# MC21R01_Power.net
KiCad netlist of a schematic drawn in Altium Designer
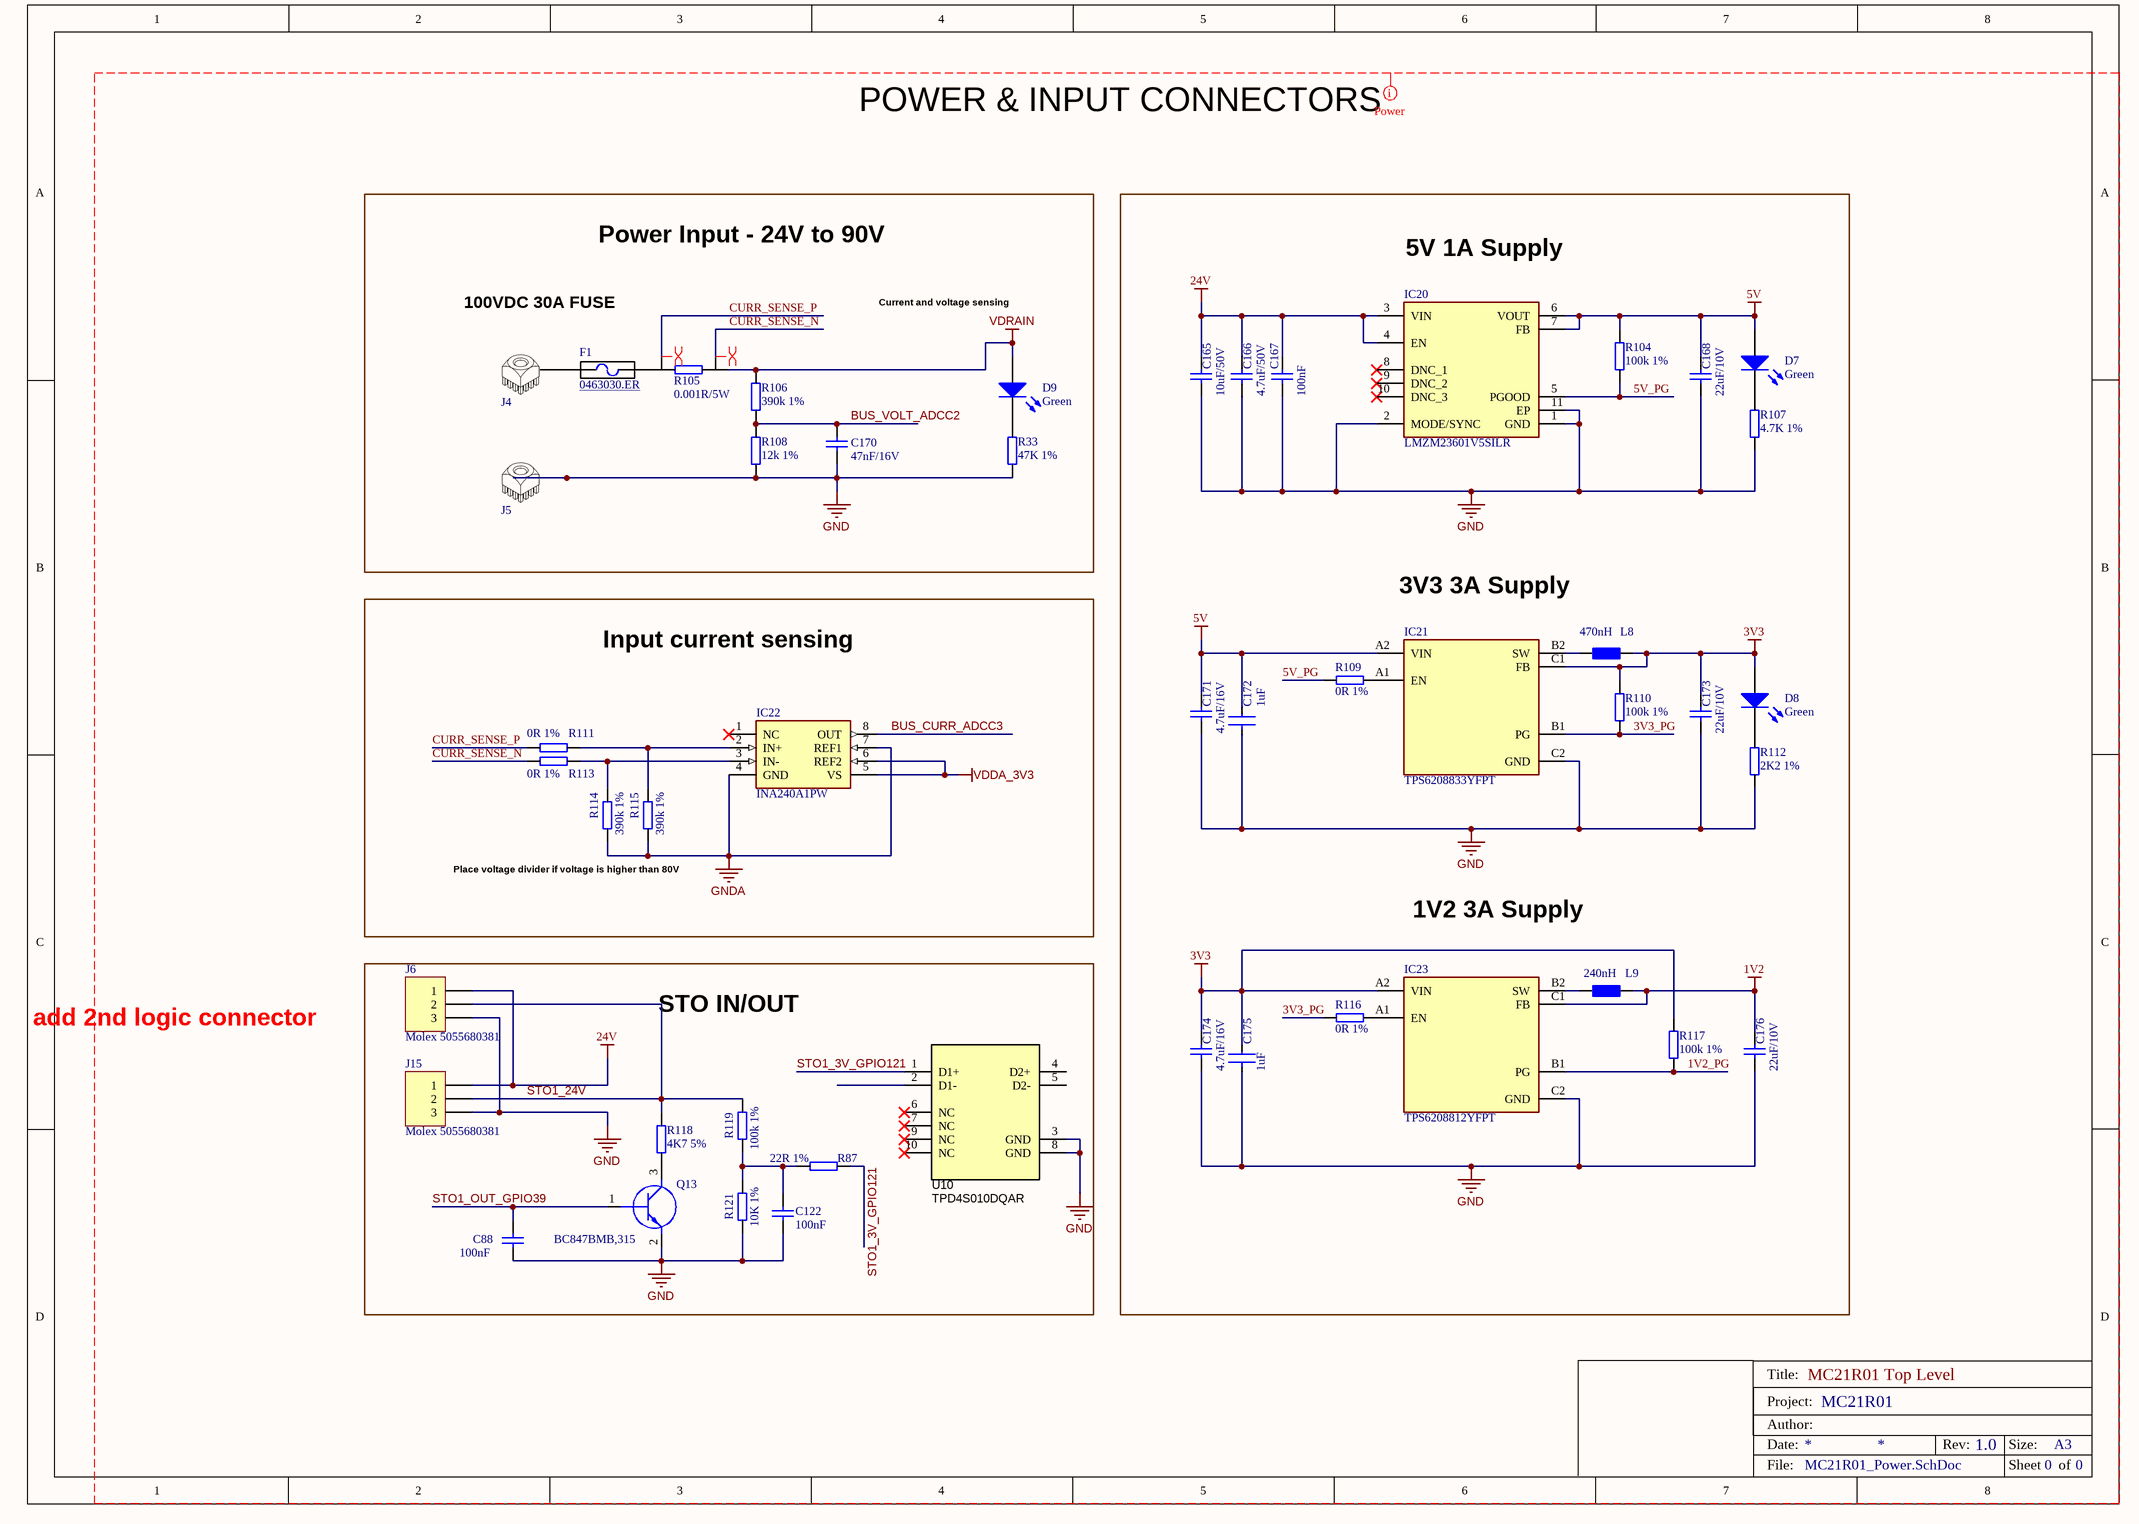
[diagram p0: MC21R01_Power.SchDoc]

(export (version "E")
  (design (tool "Eeschema 10.0.6"))
  (components
    (comp (ref "C88")
      (value "100nF")
      (footprint "CAPC0603X03N")
      (description "100nF/25V 0201 10% Tolerance X6S Multilayer Ceramic Chip Capacitor")
      (fields (field (name "TOLERANCE") "10%") (field (name "Comment") "100nF/25V 0201 10% X6S"))
      (libsource (lib "Wandercraft") (part "STD_CAP_2PIN_NPOL"))
    )
    (comp (ref "C122")
      (value "100nF")
      (footprint "CAPC0603X03N")
      (description "100nF/25V 0201 10% Tolerance X6S Multilayer Ceramic Chip Capacitor")
      (fields (field (name "TOLERANCE") "10%") (field (name "Comment") "100nF/25V 0201 10% X6S"))
      (libsource (lib "Wandercraft") (part "STD_CAP_2PIN_NPOL"))
    )
    (comp (ref "C165")
      (value "10uF/50V")
      (footprint "PAL_Capacitors:1206 SMD Capacitor")
      (description "10 uF 50 V 1206 ±10% Tolerance X5R Multilayer Ceramic Chip Capacitor")
      (fields (field (name "Comment") "10uf/50V 1206 10% X5R"))
      (libsource (lib "PAL_Capacitors") (part "10uF/50V 1206 10% X5R"))
    )
    (comp (ref "C166")
      (value "4.7uF/50V")
      (footprint "PAL_Capacitors:0805 SMD capacitor")
      (description "4.7uF 50 V 0805 ±10% Tolerance X5R Multilayer Ceramic Chip Capacitor")
      (fields (field (name "Comment") "4.7uf/50V 0805 10% X5R"))
      (libsource (lib "PAL_Capacitors") (part "4.7uF/50V 0805 10% X5R"))
    )
    (comp (ref "C167")
      (value "100nF")
      (footprint "CAPC0603X03N")
      (description "100nF/25V 0201 10% Tolerance X6S Multilayer Ceramic Chip Capacitor")
      (fields (field (name "TOLERANCE") "10%") (field (name "Comment") "100nF/25V 0201 10% X6S"))
      (libsource (lib "Wandercraft") (part "STD_CAP_2PIN_NPOL"))
    )
    (comp (ref "C168")
      (value "22uF/10V")
      (footprint "PAL_Capacitors:0603 SMD capacitor")
      (description "22 uF 10 V 0603 ±20% Tolerance X5R Multilayer Ceramic Chip Capacitor")
      (fields (field (name "Comment") "22uF/10V 0603 20% X5R"))
      (libsource (lib "PAL_Capacitors") (part "22uF/10V 0603 20% X5R"))
    )
    (comp (ref "C170")
      (value "47nF/16V")
      (footprint "PAL_Capacitors:0402 SMD Capacitor")
      (description "47nF/16V 0402 10% Tolerance X7R Multilayer Ceramic Chip Capacitor")
      (fields (field (name "Comment") "47nF/16V 0402 10% X7R"))
      (libsource (lib "PAL_Capacitors") (part "47nF/16V 0402 10% X7R"))
    )
    (comp (ref "C171")
      (value "4.7uF/16V")
      (footprint "PAL_Capacitors:0603 SMD capacitor")
      (description "4.7uF/16V 0603 10% Tolerance X5R Multilayer Ceramic Chip Capacitor")
      (fields (field (name "Comment") "4.7uF/16V 0603 10% X5R"))
      (libsource (lib "PAL_Capacitors") (part "4.7uF/16V 0603 10% X5R"))
    )
    (comp (ref "C172")
      (value "1uF/6.3V 0201 10% X5R")
      (footprint "FP-CL03-IPC_A")
      (description "1uF/6.3V 0201 10% Tolerance X5R Multilayer Ceramic Chip Capacitor")
      (fields (field (name "TOLERANCE") "20%") (field (name "CAPACITANCE") "1uF"))
      (libsource (lib "Altium Content Vault") (part "b4654b650e69147ec39a6b967a45e02"))
    )
    (comp (ref "C173")
      (value "22uF/10V")
      (footprint "PAL_Capacitors:0603 SMD capacitor")
      (description "22 uF 10 V 0603 ±20% Tolerance X5R Multilayer Ceramic Chip Capacitor")
      (fields (field (name "Comment") "22uF/10V 0603 20% X5R"))
      (libsource (lib "PAL_Capacitors") (part "22uF/10V 0603 20% X5R"))
    )
    (comp (ref "C174")
      (value "4.7uF/16V")
      (footprint "PAL_Capacitors:0603 SMD capacitor")
      (description "4.7uF/16V 0603 10% Tolerance X5R Multilayer Ceramic Chip Capacitor")
      (fields (field (name "Comment") "4.7uF/16V 0603 10% X5R"))
      (libsource (lib "PAL_Capacitors") (part "4.7uF/16V 0603 10% X5R"))
    )
    (comp (ref "C175")
      (value "1uF/6.3V 0201 10% X5R")
      (footprint "FP-CL03-IPC_A")
      (description "1uF/6.3V 0201 10% Tolerance X5R Multilayer Ceramic Chip Capacitor")
      (fields (field (name "TOLERANCE") "20%") (field (name "CAPACITANCE") "1uF"))
      (libsource (lib "Altium Content Vault") (part "b4654b650e69147ec39a6b967a45e02"))
    )
    (comp (ref "C176")
      (value "22uF/10V")
      (footprint "PAL_Capacitors:0603 SMD capacitor")
      (description "22 uF 10 V 0603 ±20% Tolerance X5R Multilayer Ceramic Chip Capacitor")
      (fields (field (name "Comment") "22uF/10V 0603 20% X5R"))
      (libsource (lib "PAL_Capacitors") (part "22uF/10V 0603 20% X5R"))
    )
    (comp (ref "D7")
      (value "Green")
      (footprint "0402 SMD LED GREEN")
      (description "Low Profile Chip LED, Green")
      (fields (field (name "MANUFACTURER") "ROHM") (field (name "MANUFACTURER PART NUMBER") "SML-P11MTT86R"))
      (libsource (lib "PAL_devices") (part "LED_0402_green"))
    )
    (comp (ref "D8")
      (value "Green")
      (footprint "0402 SMD LED GREEN")
      (description "Low Profile Chip LED, Green")
      (fields (field (name "MANUFACTURER") "ROHM") (field (name "MANUFACTURER PART NUMBER") "SML-P11MTT86R"))
      (libsource (lib "PAL_devices") (part "LED_0402_green"))
    )
    (comp (ref "D9")
      (value "Green")
      (footprint "0402 SMD LED GREEN")
      (description "Low Profile Chip LED, Green")
      (fields (field (name "MANUFACTURER") "ROHM") (field (name "MANUFACTURER PART NUMBER") "SML-P11MTT86R"))
      (libsource (lib "PAL_devices") (part "LED_0402_green"))
    )
    (comp (ref "F1")
      (value "0463030.ER")
      (footprint "0463030.ER")
      (description "LITTELFUSE - 0463030.ER - 100VDC 30A FUSE SMD")
      (libsource (lib "PAL_devices") (part "0463030.ER"))
    )
    (comp (ref "IC20")
      (value "LMZM23601V5SILR")
      (footprint "PAL_devices:LMZM23601V5SILR")
      (description "5V 1A Step-down regulator. 4V to 36V input, 5V fixed output")
      (libsource (lib "PAL_devices") (part "LMZM23601V5SILR"))
    )
    (comp (ref "IC21")
      (value "TPS6208833YFPT")
      (footprint "PAL_IPC-7351B_Footprints:BGA6C40P2X3_80X120X50")
      (description "3.3V 3A Step-Down converter")
      (libsource (lib "PAL_devices") (part "TPS6208833YFPT"))
    )
    (comp (ref "IC22")
      (value "INA240A1PW")
      (footprint "PAL_IPC-7351B_Footprints:SOP65P640X120-8N")
      (description "20V/V current sense amplifier")
      (libsource (lib "PAL_devices") (part "INA240A1PW"))
    )
    (comp (ref "IC23")
      (value "TPS6208812YFPT")
      (footprint "PAL_IPC-7351B_Footprints:BGA6C40P2X3_80X120X50")
      (description "1.2V 3A Step-Down converter")
      (libsource (lib "PAL_devices") (part "TPS6208812YFPT"))
    )
    (comp (ref "J4")
      (value "WE_7461094")
      (footprint "WE_7461094")
      (description "REDCUBE PRESS-FIT with external thread and full plain pin-plate WPSHFU, 130A, M3 screw, 9pins")
      (fields
        (field (name "MANUFACTURER") "WURTH ELEKTRONIK")
        (field (name "MANUFACTURER PART NUMBER") "7461094")
        (field (name "CREATED BY") "Yaiza Montes")
      )
      (libsource (lib "PAL_Wurth_2020") (part "WE_7461094"))
    )
    (comp (ref "J5")
      (value "WE_7461094")
      (footprint "WE_7461094")
      (description "REDCUBE PRESS-FIT with external thread and full plain pin-plate WPSHFU, 130A, M3 screw, 9pins")
      (fields
        (field (name "MANUFACTURER") "WURTH ELEKTRONIK")
        (field (name "MANUFACTURER PART NUMBER") "7461094")
        (field (name "CREATED BY") "Yaiza Montes")
      )
      (libsource (lib "PAL_Wurth_2020") (part "WE_7461094"))
    )
    (comp (ref "J6")
      (value "Molex 5055680381")
      (footprint "Molex 5055680381")
      (fields
        (field (name "MANUFACTURER") "Molex")
        (field (name "MANUFACTURER PART NUMBER") "5055680381")
        (field (name "MATING PART NUMBER") "Molex 5055650301")
        (field (name "CREATED BY") "Yaiza Montes")
      )
      (libsource (lib "PAL_Molex_Micro-Lock_2020") (part "Molex 5055680381"))
    )
    (comp (ref "J15")
      (value "Molex 5055680381")
      (footprint "Molex 5055680381")
      (fields
        (field (name "MANUFACTURER") "Molex")
        (field (name "MANUFACTURER PART NUMBER") "5055680381")
        (field (name "MATING PART NUMBER") "Molex 5055650301")
        (field (name "CREATED BY") "Yaiza Montes")
      )
      (libsource (lib "PAL_Molex_Micro-Lock_2020") (part "Molex 5055680381"))
    )
    (comp (ref "L8")
      (value "470nH")
      (footprint "PAL_Inductors:0603 SMD inductor")
      (description "Inductor, 470nH, 0603 [1608 Metric], 2.6 A, 0.054 ohm, ± 20%")
      (fields (field (name "MPN") "DFE18SANR47MG0L") (field (name "MF") "MURATA"))
      (libsource (lib "PAL_Inductors") (part "470nH/3.2A, 0603 , 2.6 A, 0.054 ohm, ± 20%"))
    )
    (comp (ref "L9")
      (value "240nH")
      (footprint "PAL_Inductors:0603 SMD inductor")
      (description "Inductor, 240nH, 0603 [1608 Metric], 3.2 A, 0.036 ohm, ± 20%")
      (fields (field (name "MPN") "DFE18SANR24ME0L") (field (name "MF") "MURATA"))
      (libsource (lib "PAL_Inductors") (part "240nH/3.2A, 0603 , 3 A, 0.036 ohm, ± 20%"))
    )
    (comp (ref "Q13")
      (value "BC847BMB,315")
      (footprint "PAL_IPC-7351B_Footprints:SOT883B")
      (description "Transistor BJT NPN")
      (fields (field (name "MOUSER PART NUMBER") "771-BC847BMB315"))
      (libsource (lib "PAL_devices") (part "BC847BMB,315"))
    )
    (comp (ref "R33")
      (value "47K 1%")
      (footprint "0402 SMD rESISTOR")
      (description "47K/50V 1% 0402 100mW SMD Resistor")
      (libsource (lib "PAL_Resistors") (part "47K/50V 1% 0402 100mW"))
    )
    (comp (ref "R87")
      (value "22R 1%")
      (footprint "0402 SMD rESISTOR")
      (description "22R/50V 1% 0402 63mW SMD Resistor")
      (libsource (lib "PAL_Resistors") (part "22R/50V 1% 0402 63mW"))
    )
    (comp (ref "R104")
      (value "100k 1%")
      (footprint "0402 SMD rESISTOR")
      (description "100k/50V 1% 0402 100mW SMD Resistor")
      (libsource (lib "PAL_Resistors") (part "100k/50V 1% 0402 100mW"))
    )
    (comp (ref "R105")
      (value "0.001R/5W")
      (footprint "PAL_Resistors:2512 SMD Resistor V2 NETTIE")
      (description "0.001R/5W 1% 2512 shunt SMD Resistor")
      (libsource (lib "PAL_Resistors") (part "0.001R/5W 1% 2512 Shunt"))
    )
    (comp (ref "R106")
      (value "390k 1%")
      (footprint "PAL_Resistors:0603 SMD resistor")
      (description "390k/150V 1% 0603 250mW SMD Resistor")
      (libsource (lib "PAL_Resistors") (part "390k/150V 1% 0603 250mW"))
    )
    (comp (ref "R107")
      (value "4.7K 1%")
      (footprint "0402 SMD rESISTOR")
      (description "4.7K/50V 1% 0402 100mW SMD Resistor")
      (libsource (lib "PAL_Resistors") (part "4.7K/50V 1% 0402 100mW"))
    )
    (comp (ref "R108")
      (value "12k 1%")
      (footprint "PAL_Resistors:0603 SMD resistor")
      (description "12k/150V 1% 0603 250mW SMD Resistor")
      (libsource (lib "PAL_Resistors") (part "12k/150V 1% 0603 250mW"))
    )
    (comp (ref "R109")
      (value "0R 1%")
      (footprint "0402 SMD rESISTOR")
      (description "0R/50V 1% 0402 100mW SMD Resistor")
      (libsource (lib "PAL_Resistors") (part "0R/50V 1% 0402 100mW"))
    )
    (comp (ref "R110")
      (value "100k 1%")
      (footprint "0402 SMD rESISTOR")
      (description "100k/50V 1% 0402 100mW SMD Resistor")
      (libsource (lib "PAL_Resistors") (part "100k/50V 1% 0402 100mW"))
    )
    (comp (ref "R111")
      (value "0R 1%")
      (footprint "0402 SMD rESISTOR")
      (description "0R/100V 1% 0402 63mW SMD Resistor")
      (libsource (lib "PAL_Resistors") (part "0R/100V 1% 0402 63mW"))
    )
    (comp (ref "R112")
      (value "2K2 1%")
      (footprint "0402 SMD rESISTOR")
      (description "2K2/50V 1% 0402 100mW SMD Resistor")
      (libsource (lib "PAL_Resistors") (part "2K2/50V 1% 0402 100mW"))
    )
    (comp (ref "R113")
      (value "0R 1%")
      (footprint "0402 SMD rESISTOR")
      (description "0R/100V 1% 0402 63mW SMD Resistor")
      (libsource (lib "PAL_Resistors") (part "0R/100V 1% 0402 63mW"))
    )
    (comp (ref "R114")
      (value "390k 1%")
      (footprint "PAL_Resistors:0603 SMD resistor")
      (description "390k/150V 1% 0603 250mW SMD Resistor")
      (libsource (lib "PAL_Resistors") (part "390k/150V 1% 0603 250mW"))
    )
    (comp (ref "R115")
      (value "390k 1%")
      (footprint "PAL_Resistors:0603 SMD resistor")
      (description "390k/150V 1% 0603 250mW SMD Resistor")
      (libsource (lib "PAL_Resistors") (part "390k/150V 1% 0603 250mW"))
    )
    (comp (ref "R116")
      (value "0R 1%")
      (footprint "0402 SMD rESISTOR")
      (description "0R/50V 1% 0402 100mW SMD Resistor")
      (libsource (lib "PAL_Resistors") (part "0R/50V 1% 0402 100mW"))
    )
    (comp (ref "R117")
      (value "100k 1%")
      (footprint "0402 SMD rESISTOR")
      (description "100k/50V 1% 0402 100mW SMD Resistor")
      (libsource (lib "PAL_Resistors") (part "100k/50V 1% 0402 100mW"))
    )
    (comp (ref "R118")
      (value "4K7 5%")
      (footprint "PAL_Resistors:0603 SMD resistor")
      (description "4K7/75V 5% 0603 100mW SMD Resistor")
      (libsource (lib "PAL_Resistors") (part "4K7/75V 5% 0603 100mW"))
    )
    (comp (ref "R119")
      (value "100k 1%")
      (footprint "0402 SMD rESISTOR")
      (description "100k/50V 1% 0402 100mW SMD Resistor")
      (libsource (lib "PAL_Resistors") (part "100k/50V 1% 0402 100mW"))
    )
    (comp (ref "R121")
      (value "10K 1%")
      (footprint "0402 SMD rESISTOR")
      (description "10K/50V 1% 0402 100mW SMD Resistor")
      (libsource (lib "PAL_Resistors") (part "10K/50V 1% 0402 100mW"))
    )
    (comp (ref "U10")
      (value "TPD4S010DQAR")
      (footprint "DQA0010A")
      (fields (field (name "MANUFACTURER") "Texas Instruments") (field (name "PARTNUMBER") "TPD4S010DQAR"))
      (libsource (lib "PAL_devices") (part "TPD4S010DQAR"))
    )
  )
  (nets
    (net (code "1") (name "/1V2_PG") (class "Default")
      (node (ref "IC23") (pin "B1") (pinfunction "PG_B1") (pintype "passive"))
      (node (ref "R117") (pin "1") (pinfunction "1_1") (pintype "passive"))
    )
    (net (code "2") (name "/3V3_PG") (class "Default")
      (node (ref "IC21") (pin "B1") (pinfunction "PG_B1") (pintype "passive"))
      (node (ref "R110") (pin "1") (pinfunction "1_1") (pintype "passive"))
      (node (ref "R116") (pin "2") (pinfunction "2_2") (pintype "passive"))
    )
    (net (code "3") (name "/5V_PG") (class "Default")
      (node (ref "IC20") (pin "5") (pinfunction "PGOOD_5") (pintype "passive"))
      (node (ref "R104") (pin "1") (pinfunction "1_1") (pintype "passive"))
      (node (ref "R109") (pin "2") (pinfunction "2_2") (pintype "passive"))
    )
    (net (code "4") (name "/BUS_CURR_ADCC3") (class "Default")
      (node (ref "IC22") (pin "8") (pinfunction "OUT_8") (pintype "output"))
    )
    (net (code "5") (name "/BUS_VOLT_ADCC2") (class "Default")
      (node (ref "C170") (pin "1") (pinfunction "1_1") (pintype "passive"))
      (node (ref "R106") (pin "1") (pinfunction "1_1") (pintype "passive"))
      (node (ref "R108") (pin "2") (pinfunction "2_2") (pintype "passive"))
    )
    (net (code "6") (name "/CURR_SENSE_N") (class "Default")
      (node (ref "R105") (pin "3") (pinfunction "3_3") (pintype "passive"))
      (node (ref "R113") (pin "1") (pinfunction "1_1") (pintype "passive"))
    )
    (net (code "7") (name "/CURR_SENSE_P") (class "Default")
      (node (ref "R105") (pin "4") (pinfunction "4_4") (pintype "passive"))
      (node (ref "R111") (pin "2") (pinfunction "2_2") (pintype "passive"))
    )
    (net (code "8") (name "/STO1_3V_GPIO121") (class "Default")
      (node (ref "R87") (pin "1") (pinfunction "1_1") (pintype "passive"))
      (node (ref "U10") (pin "1") (pinfunction "D1+_1") (pintype "passive"))
    )
    (net (code "9") (name "/STO1_24V") (class "Default")
      (node (ref "J15") (pin "2") (pinfunction "2_2") (pintype "passive"))
      (node (ref "J6") (pin "2") (pinfunction "2_2") (pintype "passive"))
      (node (ref "R118") (pin "2") (pinfunction "2_2") (pintype "passive"))
      (node (ref "R119") (pin "2") (pinfunction "2_2") (pintype "passive"))
    )
    (net (code "10") (name "/STO1_OUT_GPIO39") (class "Default")
      (node (ref "C88") (pin "2") (pinfunction "2_2") (pintype "passive"))
      (node (ref "Q13") (pin "1") (pinfunction "B_1") (pintype "passive"))
    )
    (net (code "11") (name "1V2") (class "Default")
      (node (ref "C176") (pin "1") (pinfunction "1_1") (pintype "passive"))
      (node (ref "IC23") (pin "C1") (pinfunction "FB_C1") (pintype "passive"))
      (node (ref "L9") (pin "1") (pinfunction "1_1") (pintype "passive"))
    )
    (net (code "12") (name "3V3") (class "Default")
      (node (ref "C173") (pin "1") (pinfunction "1_1") (pintype "passive"))
      (node (ref "C174") (pin "1") (pinfunction "1_1") (pintype "passive"))
      (node (ref "C175") (pin "2") (pinfunction "2_2") (pintype "passive"))
      (node (ref "D8") (pin "A") (pinfunction "A_A") (pintype "passive"))
      (node (ref "IC21") (pin "C1") (pinfunction "FB_C1") (pintype "passive"))
      (node (ref "IC23") (pin "A2") (pinfunction "VIN_A2") (pintype "passive"))
      (node (ref "L8") (pin "1") (pinfunction "1_1") (pintype "passive"))
      (node (ref "R110") (pin "2") (pinfunction "2_2") (pintype "passive"))
      (node (ref "R117") (pin "2") (pinfunction "2_2") (pintype "passive"))
    )
    (net (code "13") (name "5V") (class "Default")
      (node (ref "C168") (pin "1") (pinfunction "1_1") (pintype "passive"))
      (node (ref "C171") (pin "1") (pinfunction "1_1") (pintype "passive"))
      (node (ref "C172") (pin "2") (pinfunction "2_2") (pintype "passive"))
      (node (ref "D7") (pin "A") (pinfunction "A_A") (pintype "passive"))
      (node (ref "IC20") (pin "6") (pinfunction "VOUT_6") (pintype "passive"))
      (node (ref "IC20") (pin "7") (pinfunction "FB_7") (pintype "passive"))
      (node (ref "IC21") (pin "A2") (pinfunction "VIN_A2") (pintype "passive"))
      (node (ref "R104") (pin "2") (pinfunction "2_2") (pintype "passive"))
    )
    (net (code "14") (name "24V") (class "Default")
      (node (ref "C165") (pin "1") (pinfunction "1_1") (pintype "passive"))
      (node (ref "C166") (pin "1") (pinfunction "1_1") (pintype "passive"))
      (node (ref "C167") (pin "2") (pinfunction "2_2") (pintype "passive"))
      (node (ref "IC20") (pin "3") (pinfunction "VIN_3") (pintype "passive"))
      (node (ref "IC20") (pin "4") (pinfunction "EN_4") (pintype "passive"))
      (node (ref "J15") (pin "1") (pinfunction "1_1") (pintype "passive"))
      (node (ref "J6") (pin "1") (pinfunction "1_1") (pintype "passive"))
    )
    (net (code "15") (name "GND") (class "Default")
      (node (ref "C122") (pin "1") (pinfunction "1_1") (pintype "passive"))
      (node (ref "C165") (pin "2") (pinfunction "2_2") (pintype "passive"))
      (node (ref "C166") (pin "2") (pinfunction "2_2") (pintype "passive"))
      (node (ref "C167") (pin "1") (pinfunction "1_1") (pintype "passive"))
      (node (ref "C168") (pin "2") (pinfunction "2_2") (pintype "passive"))
      (node (ref "C170") (pin "2") (pinfunction "2_2") (pintype "passive"))
      (node (ref "C171") (pin "2") (pinfunction "2_2") (pintype "passive"))
      (node (ref "C172") (pin "1") (pinfunction "1_1") (pintype "passive"))
      (node (ref "C173") (pin "2") (pinfunction "2_2") (pintype "passive"))
      (node (ref "C174") (pin "2") (pinfunction "2_2") (pintype "passive"))
      (node (ref "C175") (pin "1") (pinfunction "1_1") (pintype "passive"))
      (node (ref "C176") (pin "2") (pinfunction "2_2") (pintype "passive"))
      (node (ref "C88") (pin "1") (pinfunction "1_1") (pintype "passive"))
      (node (ref "IC20") (pin "1") (pinfunction "GND_1") (pintype "passive"))
      (node (ref "IC20") (pin "11") (pinfunction "EP_11") (pintype "passive"))
      (node (ref "IC20") (pin "2") (pinfunction "MODE/SYNC_2") (pintype "passive"))
      (node (ref "IC21") (pin "C2") (pinfunction "GND_C2") (pintype "passive"))
      (node (ref "IC23") (pin "C2") (pinfunction "GND_C2") (pintype "passive"))
      (node (ref "J15") (pin "3") (pinfunction "3_3") (pintype "passive"))
      (node (ref "J5") (pin "1") (pinfunction "1_1") (pintype "passive"))
      (node (ref "J6") (pin "3") (pinfunction "3_3") (pintype "passive"))
      (node (ref "Q13") (pin "2") (pinfunction "E_2") (pintype "passive"))
      (node (ref "R107") (pin "1") (pinfunction "1_1") (pintype "passive"))
      (node (ref "R108") (pin "1") (pinfunction "1_1") (pintype "passive"))
      (node (ref "R112") (pin "1") (pinfunction "1_1") (pintype "passive"))
      (node (ref "R121") (pin "1") (pinfunction "1_1") (pintype "passive"))
      (node (ref "R33") (pin "1") (pinfunction "1_1") (pintype "passive"))
      (node (ref "U10") (pin "3") (pinfunction "GND_3") (pintype "power_in"))
      (node (ref "U10") (pin "8") (pinfunction "GND_8") (pintype "power_in"))
    )
    (net (code "16") (name "GNDA") (class "Default")
      (node (ref "IC22") (pin "4") (pinfunction "GND_4") (pintype "power_in"))
      (node (ref "IC22") (pin "7") (pinfunction "REF1_7") (pintype "input"))
      (node (ref "R114") (pin "1") (pinfunction "1_1") (pintype "passive"))
      (node (ref "R115") (pin "1") (pinfunction "1_1") (pintype "passive"))
    )
    (net (code "17") (name "Net-(C122-Pad2)") (class "Default")
      (node (ref "C122") (pin "2") (pinfunction "2_2") (pintype "passive"))
      (node (ref "R119") (pin "1") (pinfunction "1_1") (pintype "passive"))
      (node (ref "R121") (pin "2") (pinfunction "2_2") (pintype "passive"))
      (node (ref "R87") (pin "2") (pinfunction "2_2") (pintype "passive"))
    )
    (net (code "18") (name "Net-(D7-PadK)") (class "Default")
      (node (ref "D7") (pin "K") (pinfunction "K_K") (pintype "passive"))
      (node (ref "R107") (pin "2") (pinfunction "2_2") (pintype "passive"))
    )
    (net (code "19") (name "Net-(D8-PadK)") (class "Default")
      (node (ref "D8") (pin "K") (pinfunction "K_K") (pintype "passive"))
      (node (ref "R112") (pin "2") (pinfunction "2_2") (pintype "passive"))
    )
    (net (code "20") (name "Net-(D9-PadK)") (class "Default")
      (node (ref "D9") (pin "K") (pinfunction "K_K") (pintype "passive"))
      (node (ref "R33") (pin "2") (pinfunction "2_2") (pintype "passive"))
    )
    (net (code "21") (name "Net-(F1-Pad1)") (class "Default")
      (node (ref "F1") (pin "1") (pinfunction "1_1") (pintype "passive"))
      (node (ref "J4") (pin "1") (pinfunction "1_1") (pintype "passive"))
    )
    (net (code "22") (name "Net-(F1-Pad2)") (class "Default")
      (node (ref "F1") (pin "2") (pinfunction "2_2") (pintype "passive"))
      (node (ref "R105") (pin "2") (pinfunction "2_2") (pintype "passive"))
    )
    (net (code "23") (name "Net-(IC21-EN)") (class "Default")
      (node (ref "IC21") (pin "A1") (pinfunction "EN_A1") (pintype "passive"))
      (node (ref "R109") (pin "1") (pinfunction "1_1") (pintype "passive"))
    )
    (net (code "24") (name "Net-(IC21-SW)") (class "Default")
      (node (ref "IC21") (pin "B2") (pinfunction "SW_B2") (pintype "passive"))
      (node (ref "L8") (pin "2") (pinfunction "2_2") (pintype "passive"))
    )
    (net (code "25") (name "Net-(IC22-IN+)") (class "Default")
      (node (ref "IC22") (pin "2") (pinfunction "IN+_2") (pintype "input"))
      (node (ref "R111") (pin "1") (pinfunction "1_1") (pintype "passive"))
      (node (ref "R115") (pin "2") (pinfunction "2_2") (pintype "passive"))
    )
    (net (code "26") (name "Net-(IC22-IN-)") (class "Default")
      (node (ref "IC22") (pin "3") (pinfunction "IN-_3") (pintype "input"))
      (node (ref "R113") (pin "2") (pinfunction "2_2") (pintype "passive"))
      (node (ref "R114") (pin "2") (pinfunction "2_2") (pintype "passive"))
    )
    (net (code "27") (name "Net-(IC23-EN)") (class "Default")
      (node (ref "IC23") (pin "A1") (pinfunction "EN_A1") (pintype "passive"))
      (node (ref "R116") (pin "1") (pinfunction "1_1") (pintype "passive"))
    )
    (net (code "28") (name "Net-(IC23-SW)") (class "Default")
      (node (ref "IC23") (pin "B2") (pinfunction "SW_B2") (pintype "passive"))
      (node (ref "L9") (pin "2") (pinfunction "2_2") (pintype "passive"))
    )
    (net (code "29") (name "Net-(Q13-C)") (class "Default")
      (node (ref "Q13") (pin "3") (pinfunction "C_3") (pintype "passive"))
      (node (ref "R118") (pin "1") (pinfunction "1_1") (pintype "passive"))
    )
    (net (code "30") (name "VDDA_3V3") (class "Default")
      (node (ref "IC22") (pin "5") (pinfunction "VS_5") (pintype "power_in"))
      (node (ref "IC22") (pin "6") (pinfunction "REF2_6") (pintype "input"))
    )
    (net (code "31") (name "VDRAIN") (class "Default")
      (node (ref "D9") (pin "A") (pinfunction "A_A") (pintype "passive"))
      (node (ref "R105") (pin "1") (pinfunction "1_1") (pintype "passive"))
      (node (ref "R106") (pin "2") (pinfunction "2_2") (pintype "passive"))
    )
    (net (code "32") (name "unconnected-(IC20-DNC_1-Pad8)") (class "Default")
      (node (ref "IC20") (pin "8") (pinfunction "DNC_1_8") (pintype "passive+no_connect"))
    )
    (net (code "33") (name "unconnected-(IC20-DNC_2-Pad9)") (class "Default")
      (node (ref "IC20") (pin "9") (pinfunction "DNC_2_9") (pintype "passive+no_connect"))
    )
    (net (code "34") (name "unconnected-(IC20-DNC_3-Pad10)") (class "Default")
      (node (ref "IC20") (pin "10") (pinfunction "DNC_3_10") (pintype "passive+no_connect"))
    )
    (net (code "35") (name "unconnected-(IC22-NC-Pad1)") (class "Default")
      (node (ref "IC22") (pin "1") (pinfunction "NC_1") (pintype "passive+no_connect"))
    )
    (net (code "36") (name "unconnected-(U10-D1--Pad2)") (class "Default")
      (node (ref "U10") (pin "2") (pinfunction "D1-_2") (pintype "passive"))
    )
    (net (code "37") (name "unconnected-(U10-D2+-Pad4)") (class "Default")
      (node (ref "U10") (pin "4") (pinfunction "D2+_4") (pintype "passive"))
    )
    (net (code "38") (name "unconnected-(U10-D2--Pad5)") (class "Default")
      (node (ref "U10") (pin "5") (pinfunction "D2-_5") (pintype "passive"))
    )
    (net (code "39") (name "unconnected-(U10-NC-Pad6)") (class "Default")
      (node (ref "U10") (pin "6") (pinfunction "NC_6") (pintype "passive+no_connect"))
    )
    (net (code "40") (name "unconnected-(U10-NC-Pad7)") (class "Default")
      (node (ref "U10") (pin "7") (pinfunction "NC_7") (pintype "passive+no_connect"))
    )
    (net (code "41") (name "unconnected-(U10-NC-Pad9)") (class "Default")
      (node (ref "U10") (pin "9") (pinfunction "NC_9") (pintype "passive+no_connect"))
    )
    (net (code "42") (name "unconnected-(U10-NC-Pad10)") (class "Default")
      (node (ref "U10") (pin "10") (pinfunction "NC_10") (pintype "passive+no_connect"))
    )
  )
)
